# ADC-Board5.net
KiCad netlist of a schematic drawn in EAGLE
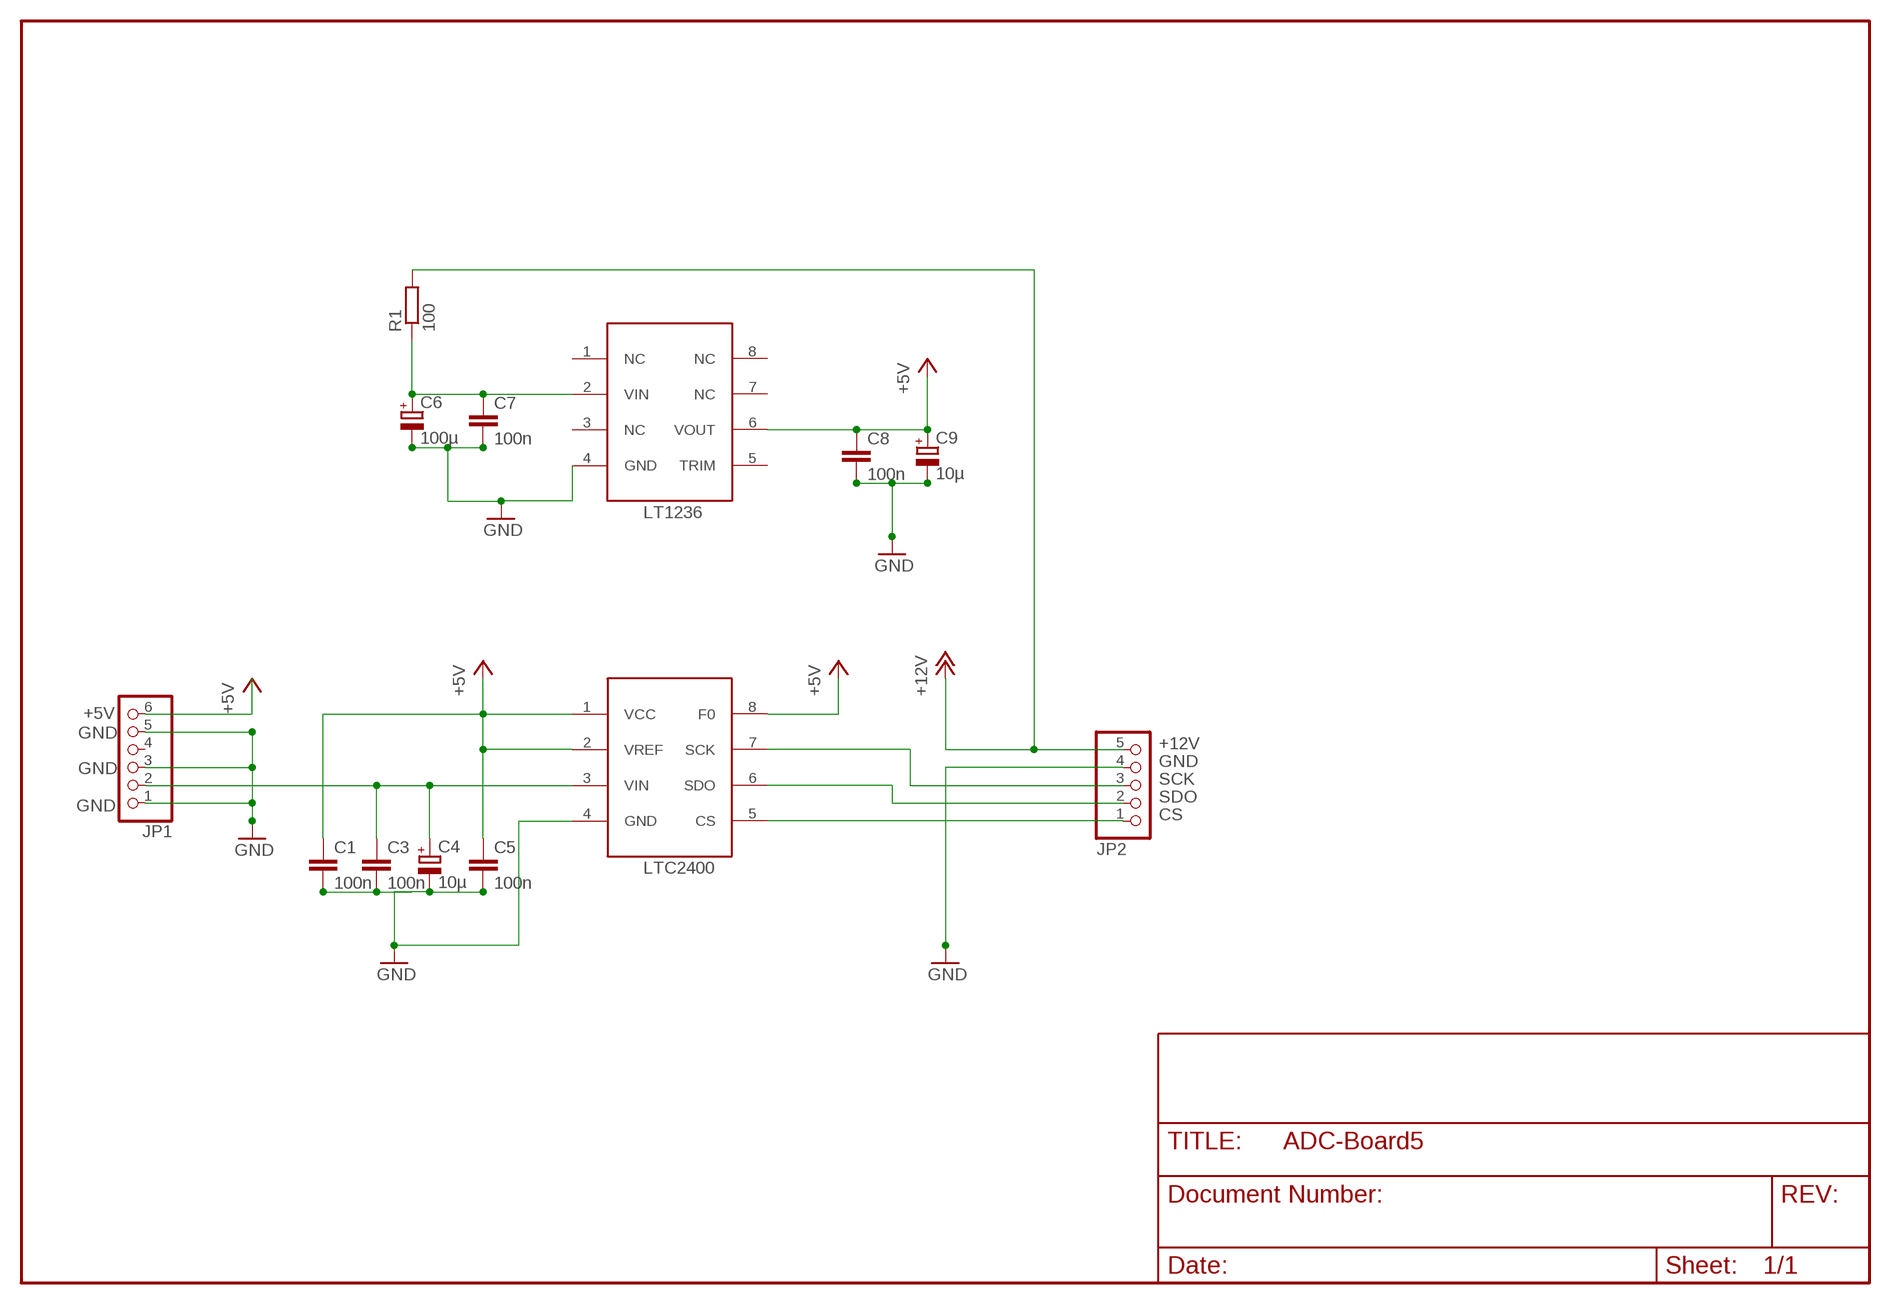
[diagram p0: schematic, sheet 1]

(export (version "E")
  (design (tool "Eeschema 10.0.6"))
  (components
    (comp (ref "C1")
      (value "100n")
      (footprint "eagle-import:C0805")
      (libsource (lib "eagle-import") (part "C-EUC0805"))
    )
    (comp (ref "C3")
      (value "100n")
      (footprint "eagle-import:C0805")
      (libsource (lib "eagle-import") (part "C-EUC0805"))
    )
    (comp (ref "C4")
      (value "10µ")
      (footprint "eagle-import:C_6032-28R")
      (libsource (lib "eagle-import") (part "CPOL-EUC/6032-28R"))
    )
    (comp (ref "C5")
      (value "100n")
      (footprint "eagle-import:C0805")
      (libsource (lib "eagle-import") (part "C-EUC0805"))
    )
    (comp (ref "C6")
      (value "100µ")
      (footprint "eagle-import:D_7343-31R")
      (libsource (lib "eagle-import") (part "CPOL-EUD/7343-31R"))
    )
    (comp (ref "C7")
      (value "100n")
      (footprint "eagle-import:C0805")
      (libsource (lib "eagle-import") (part "C-EUC0805"))
    )
    (comp (ref "C8")
      (value "100n")
      (footprint "eagle-import:C0805")
      (libsource (lib "eagle-import") (part "C-EUC0805"))
    )
    (comp (ref "C9")
      (value "10µ")
      (footprint "eagle-import:C_6032-28R")
      (libsource (lib "eagle-import") (part "CPOL-EUC/6032-28R"))
    )
    (comp (ref "IC1")
      (value "LT1236")
      (footprint "eagle-import:SO08")
      (libsource (lib "eagle-import") (part "LT1236"))
    )
    (comp (ref "IC2")
      (value "LTC2400")
      (footprint "eagle-import:SO08")
      (libsource (lib "eagle-import") (part "LTC2400"))
    )
    (comp (ref "JP1")
      (value "PINHD-1X6")
      (footprint "eagle-import:1X06")
      (libsource (lib "eagle-import") (part "PINHD-1X6"))
    )
    (comp (ref "JP2")
      (value "PINHD-1X5")
      (footprint "eagle-import:1X05")
      (libsource (lib "eagle-import") (part "PINHD-1X5"))
    )
    (comp (ref "R1")
      (value "100")
      (footprint "eagle-import:M1206")
      (libsource (lib "eagle-import") (part "R-EU_M1206"))
    )
  )
  (nets
    (net (code "1") (name "+5V") (class "Default")
      (node (ref "C1") (pin "1") (pinfunction "1_1") (pintype "passive"))
      (node (ref "C5") (pin "1") (pinfunction "1_1") (pintype "passive"))
      (node (ref "C8") (pin "1") (pinfunction "1_1") (pintype "passive"))
      (node (ref "C9") (pin "+") (pinfunction "+_+") (pintype "passive"))
      (node (ref "IC1") (pin "6") (pinfunction "VOUT_6") (pintype "bidirectional"))
      (node (ref "IC2") (pin "1") (pinfunction "VCC_1") (pintype "bidirectional"))
      (node (ref "IC2") (pin "2") (pinfunction "VREF_2") (pintype "bidirectional"))
      (node (ref "IC2") (pin "8") (pinfunction "F0_8") (pintype "bidirectional"))
      (node (ref "JP1") (pin "6") (pinfunction "6_6") (pintype "passive"))
    )
    (net (code "2") (name "+12V") (class "Default")
      (node (ref "JP2") (pin "5") (pinfunction "5_5") (pintype "passive"))
      (node (ref "R1") (pin "2") (pinfunction "2_2") (pintype "passive"))
    )
    (net (code "3") (name "/CS") (class "Default")
      (node (ref "IC2") (pin "5") (pinfunction "CS_5") (pintype "bidirectional"))
      (node (ref "JP2") (pin "1") (pinfunction "1_1") (pintype "passive"))
    )
    (net (code "4") (name "/SCK") (class "Default")
      (node (ref "IC2") (pin "7") (pinfunction "SCK_7") (pintype "bidirectional"))
      (node (ref "JP2") (pin "3") (pinfunction "3_3") (pintype "passive"))
    )
    (net (code "5") (name "/SDO") (class "Default")
      (node (ref "IC2") (pin "6") (pinfunction "SDO_6") (pintype "bidirectional"))
      (node (ref "JP2") (pin "2") (pinfunction "2_2") (pintype "passive"))
    )
    (net (code "6") (name "GND") (class "Default")
      (node (ref "C1") (pin "2") (pinfunction "2_2") (pintype "passive"))
      (node (ref "C3") (pin "2") (pinfunction "2_2") (pintype "passive"))
      (node (ref "C4") (pin "-") (pinfunction "-_-") (pintype "passive"))
      (node (ref "C5") (pin "2") (pinfunction "2_2") (pintype "passive"))
      (node (ref "C6") (pin "-") (pinfunction "-_-") (pintype "passive"))
      (node (ref "C7") (pin "2") (pinfunction "2_2") (pintype "passive"))
      (node (ref "C8") (pin "2") (pinfunction "2_2") (pintype "passive"))
      (node (ref "C9") (pin "-") (pinfunction "-_-") (pintype "passive"))
      (node (ref "IC1") (pin "4") (pinfunction "GND_4") (pintype "bidirectional"))
      (node (ref "IC2") (pin "4") (pinfunction "GND_4") (pintype "bidirectional"))
      (node (ref "JP1") (pin "1") (pinfunction "1_1") (pintype "passive"))
      (node (ref "JP1") (pin "3") (pinfunction "3_3") (pintype "passive"))
      (node (ref "JP1") (pin "5") (pinfunction "5_5") (pintype "passive"))
      (node (ref "JP2") (pin "4") (pinfunction "4_4") (pintype "passive"))
    )
    (net (code "7") (name "Net-(IC1-VIN)") (class "Default")
      (node (ref "C6") (pin "+") (pinfunction "+_+") (pintype "passive"))
      (node (ref "C7") (pin "1") (pinfunction "1_1") (pintype "passive"))
      (node (ref "IC1") (pin "2") (pinfunction "VIN_2") (pintype "bidirectional"))
      (node (ref "R1") (pin "1") (pinfunction "1_1") (pintype "passive"))
    )
    (net (code "8") (name "Net-(IC2-VIN)") (class "Default")
      (node (ref "C3") (pin "1") (pinfunction "1_1") (pintype "passive"))
      (node (ref "C4") (pin "+") (pinfunction "+_+") (pintype "passive"))
      (node (ref "IC2") (pin "3") (pinfunction "VIN_3") (pintype "bidirectional"))
      (node (ref "JP1") (pin "2") (pinfunction "2_2") (pintype "passive"))
    )
    (net (code "9") (name "unconnected-(IC1-NC-Pad1)") (class "Default")
      (node (ref "IC1") (pin "1") (pinfunction "NC_1") (pintype "bidirectional"))
    )
    (net (code "10") (name "unconnected-(IC1-NC-Pad3)") (class "Default")
      (node (ref "IC1") (pin "3") (pinfunction "NC_3") (pintype "bidirectional"))
    )
    (net (code "11") (name "unconnected-(IC1-NC-Pad7)") (class "Default")
      (node (ref "IC1") (pin "7") (pinfunction "NC_7") (pintype "bidirectional"))
    )
    (net (code "12") (name "unconnected-(IC1-NC-Pad8)") (class "Default")
      (node (ref "IC1") (pin "8") (pinfunction "NC_8") (pintype "bidirectional"))
    )
    (net (code "13") (name "unconnected-(IC1-TRIM-Pad5)") (class "Default")
      (node (ref "IC1") (pin "5") (pinfunction "TRIM_5") (pintype "bidirectional"))
    )
    (net (code "14") (name "unconnected-(JP1-Pad4)") (class "Default")
      (node (ref "JP1") (pin "4") (pinfunction "4_4") (pintype "passive"))
    )
  )
)
